# counter-mega8.net
KiCad netlist of a schematic drawn in EAGLE
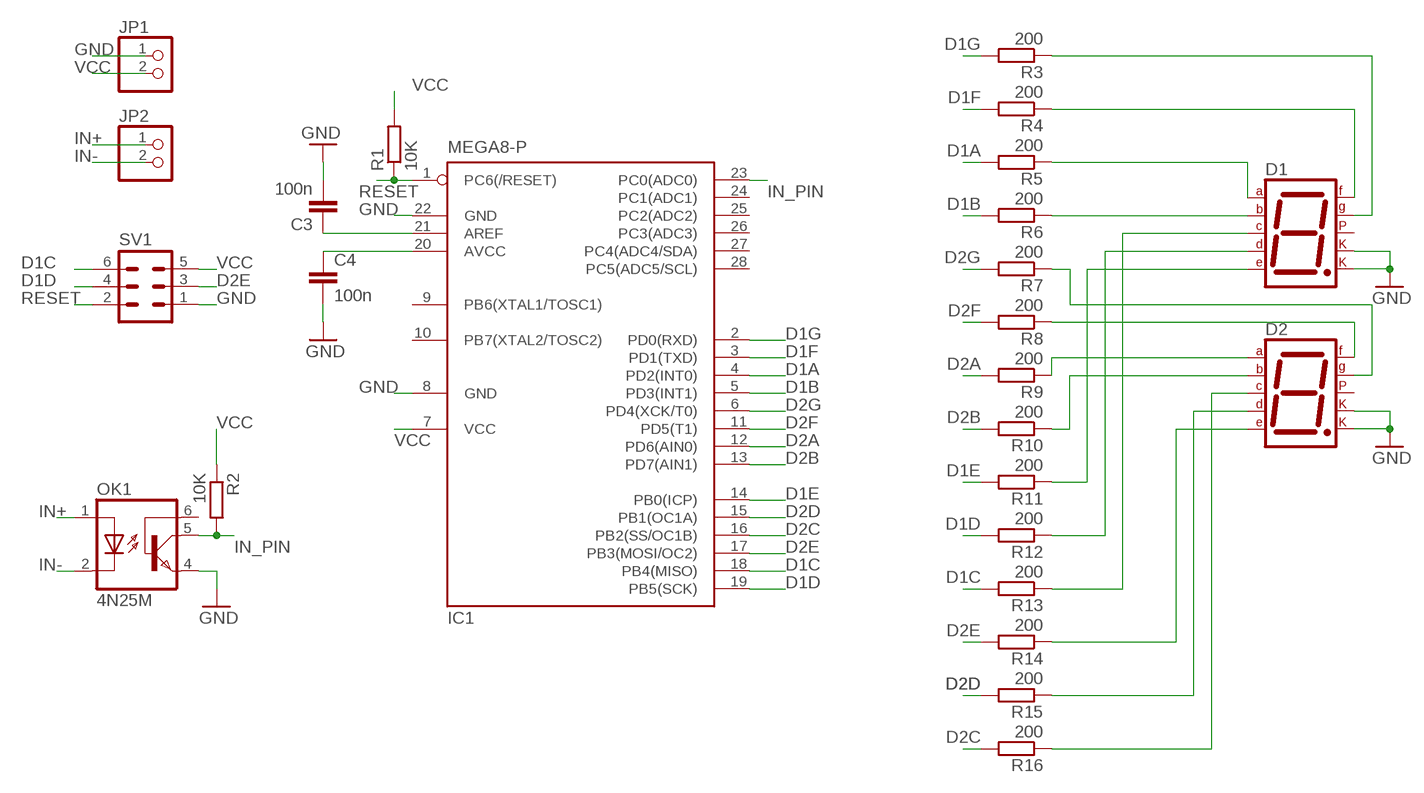
[diagram p0: schematic, sheet 1]

(export (version "E")
  (design (tool "Eeschema 10.0.6"))
  (components
    (comp (ref "C3")
      (value "100n")
      (footprint "eagle-import:C1206")
      (libsource (lib "eagle-import") (part "C-EUC1206"))
    )
    (comp (ref "C4")
      (value "100n")
      (footprint "eagle-import:C1206")
      (libsource (lib "eagle-import") (part "C-EUC1206"))
    )
    (comp (ref "D1")
      (value "7SEG-CK")
      (footprint "eagle-import:7SEG-13")
      (libsource (lib "eagle-import") (part "7SEG-CK"))
    )
    (comp (ref "D2")
      (value "7SEG-CK")
      (footprint "eagle-import:7SEG-13")
      (libsource (lib "eagle-import") (part "7SEG-CK"))
    )
    (comp (ref "IC1")
      (value "MEGA8-P")
      (footprint "eagle-import:DIL28-3")
      (libsource (lib "eagle-import") (part "MEGA8-P"))
    )
    (comp (ref "JP1")
      (value "PINHD-1X2/90")
      (footprint "eagle-import:1X02_90")
      (libsource (lib "eagle-import") (part "PINHD-1X2/90"))
    )
    (comp (ref "JP2")
      (value "PINHD-1X2/90")
      (footprint "eagle-import:1X02_90")
      (libsource (lib "eagle-import") (part "PINHD-1X2/90"))
    )
    (comp (ref "OK1")
      (value "4N25M")
      (footprint "eagle-import:DIL06")
      (fields (field (name "MPN") "4N25-M"))
      (libsource (lib "eagle-import") (part "4N?M25"))
    )
    (comp (ref "R1")
      (value "10K")
      (footprint "eagle-import:R1206")
      (libsource (lib "eagle-import") (part "R-EU_R1206"))
    )
    (comp (ref "R2")
      (value "10K")
      (footprint "eagle-import:R1206")
      (libsource (lib "eagle-import") (part "R-EU_R1206"))
    )
    (comp (ref "R3")
      (value "200")
      (footprint "eagle-import:R1206")
      (libsource (lib "eagle-import") (part "R-EU_R1206"))
    )
    (comp (ref "R4")
      (value "200")
      (footprint "eagle-import:R1206")
      (libsource (lib "eagle-import") (part "R-EU_R1206"))
    )
    (comp (ref "R5")
      (value "200")
      (footprint "eagle-import:R1206")
      (libsource (lib "eagle-import") (part "R-EU_R1206"))
    )
    (comp (ref "R6")
      (value "200")
      (footprint "eagle-import:R1206")
      (libsource (lib "eagle-import") (part "R-EU_R1206"))
    )
    (comp (ref "R7")
      (value "200")
      (footprint "eagle-import:R1206")
      (libsource (lib "eagle-import") (part "R-EU_R1206"))
    )
    (comp (ref "R8")
      (value "200")
      (footprint "eagle-import:R1206")
      (libsource (lib "eagle-import") (part "R-EU_R1206"))
    )
    (comp (ref "R9")
      (value "200")
      (footprint "eagle-import:R1206")
      (libsource (lib "eagle-import") (part "R-EU_R1206"))
    )
    (comp (ref "R10")
      (value "200")
      (footprint "eagle-import:R1206")
      (libsource (lib "eagle-import") (part "R-EU_R1206"))
    )
    (comp (ref "R11")
      (value "200")
      (footprint "eagle-import:R1206")
      (libsource (lib "eagle-import") (part "R-EU_R1206"))
    )
    (comp (ref "R12")
      (value "200")
      (footprint "eagle-import:R1206")
      (libsource (lib "eagle-import") (part "R-EU_R1206"))
    )
    (comp (ref "R13")
      (value "200")
      (footprint "eagle-import:R1206")
      (libsource (lib "eagle-import") (part "R-EU_R1206"))
    )
    (comp (ref "R14")
      (value "200")
      (footprint "eagle-import:R1206")
      (libsource (lib "eagle-import") (part "R-EU_R1206"))
    )
    (comp (ref "R15")
      (value "200")
      (footprint "eagle-import:R1206")
      (libsource (lib "eagle-import") (part "R-EU_R1206"))
    )
    (comp (ref "R16")
      (value "200")
      (footprint "eagle-import:R1206")
      (libsource (lib "eagle-import") (part "R-EU_R1206"))
    )
    (comp (ref "SV1")
      (value "MA03-2")
      (footprint "eagle-import:MA03-2")
      (libsource (lib "eagle-import") (part "MA03-2"))
    )
  )
  (nets
    (net (code "1") (name "/D1A") (class "Default")
      (node (ref "IC1") (pin "4") (pinfunction "PD2(INT0)_4") (pintype "bidirectional"))
      (node (ref "R5") (pin "2") (pinfunction "2_2") (pintype "passive"))
    )
    (net (code "2") (name "/D1B") (class "Default")
      (node (ref "IC1") (pin "5") (pinfunction "PD3(INT1)_5") (pintype "bidirectional"))
      (node (ref "R6") (pin "2") (pinfunction "2_2") (pintype "passive"))
    )
    (net (code "3") (name "/D1C") (class "Default")
      (node (ref "IC1") (pin "18") (pinfunction "PB4(MISO)_18") (pintype "bidirectional"))
      (node (ref "R13") (pin "2") (pinfunction "2_2") (pintype "passive"))
      (node (ref "SV1") (pin "6") (pinfunction "6_6") (pintype "passive"))
    )
    (net (code "4") (name "/D1D") (class "Default")
      (node (ref "IC1") (pin "19") (pinfunction "PB5(SCK)_19") (pintype "bidirectional"))
      (node (ref "R12") (pin "2") (pinfunction "2_2") (pintype "passive"))
      (node (ref "SV1") (pin "4") (pinfunction "4_4") (pintype "passive"))
    )
    (net (code "5") (name "/D1E") (class "Default")
      (node (ref "IC1") (pin "14") (pinfunction "PB0(ICP)_14") (pintype "bidirectional"))
      (node (ref "R11") (pin "2") (pinfunction "2_2") (pintype "passive"))
    )
    (net (code "6") (name "/D1F") (class "Default")
      (node (ref "IC1") (pin "3") (pinfunction "PD1(TXD)_3") (pintype "bidirectional"))
      (node (ref "R4") (pin "2") (pinfunction "2_2") (pintype "passive"))
    )
    (net (code "7") (name "/D1G") (class "Default")
      (node (ref "IC1") (pin "2") (pinfunction "PD0(RXD)_2") (pintype "bidirectional"))
      (node (ref "R3") (pin "2") (pinfunction "2_2") (pintype "passive"))
    )
    (net (code "8") (name "/D2A") (class "Default")
      (node (ref "IC1") (pin "12") (pinfunction "PD6(AIN0)_12") (pintype "bidirectional"))
      (node (ref "R9") (pin "2") (pinfunction "2_2") (pintype "passive"))
    )
    (net (code "9") (name "/D2B") (class "Default")
      (node (ref "IC1") (pin "13") (pinfunction "PD7(AIN1)_13") (pintype "bidirectional"))
      (node (ref "R10") (pin "2") (pinfunction "2_2") (pintype "passive"))
    )
    (net (code "10") (name "/D2C") (class "Default")
      (node (ref "IC1") (pin "16") (pinfunction "PB2(SS/OC1B)_16") (pintype "bidirectional"))
      (node (ref "R16") (pin "2") (pinfunction "2_2") (pintype "passive"))
    )
    (net (code "11") (name "/D2D") (class "Default")
      (node (ref "IC1") (pin "15") (pinfunction "PB1(OC1A)_15") (pintype "bidirectional"))
      (node (ref "R15") (pin "2") (pinfunction "2_2") (pintype "passive"))
    )
    (net (code "12") (name "/D2E") (class "Default")
      (node (ref "IC1") (pin "17") (pinfunction "PB3(MOSI/OC2)_17") (pintype "bidirectional"))
      (node (ref "R14") (pin "2") (pinfunction "2_2") (pintype "passive"))
      (node (ref "SV1") (pin "3") (pinfunction "3_3") (pintype "passive"))
    )
    (net (code "13") (name "/D2F") (class "Default")
      (node (ref "IC1") (pin "11") (pinfunction "PD5(T1)_11") (pintype "bidirectional"))
      (node (ref "R8") (pin "2") (pinfunction "2_2") (pintype "passive"))
    )
    (net (code "14") (name "/D2G") (class "Default")
      (node (ref "IC1") (pin "6") (pinfunction "PD4(XCK/T0)_6") (pintype "bidirectional"))
      (node (ref "R7") (pin "2") (pinfunction "2_2") (pintype "passive"))
    )
    (net (code "15") (name "/IN+") (class "Default")
      (node (ref "JP2") (pin "1") (pinfunction "1_1") (pintype "passive"))
      (node (ref "OK1") (pin "1") (pinfunction "A_1") (pintype "passive"))
    )
    (net (code "16") (name "/IN-") (class "Default")
      (node (ref "JP2") (pin "2") (pinfunction "2_2") (pintype "passive"))
      (node (ref "OK1") (pin "2") (pinfunction "C_2") (pintype "passive"))
    )
    (net (code "17") (name "/IN_PIN") (class "Default")
      (node (ref "IC1") (pin "23") (pinfunction "PC0(ADC0)_23") (pintype "bidirectional"))
      (node (ref "OK1") (pin "5") (pinfunction "COL_5") (pintype "passive"))
      (node (ref "R2") (pin "2") (pinfunction "2_2") (pintype "passive"))
    )
    (net (code "18") (name "/RESET") (class "Default")
      (node (ref "IC1") (pin "1") (pinfunction "PC6(/RESET)_1") (pintype "bidirectional"))
      (node (ref "R1") (pin "1") (pinfunction "1_1") (pintype "passive"))
      (node (ref "SV1") (pin "2") (pinfunction "2_2") (pintype "passive"))
    )
    (net (code "19") (name "/VCC") (class "Default")
      (node (ref "IC1") (pin "7") (pinfunction "VCC_7") (pintype "power_in"))
      (node (ref "JP1") (pin "2") (pinfunction "2_2") (pintype "passive"))
      (node (ref "R1") (pin "2") (pinfunction "2_2") (pintype "passive"))
      (node (ref "R2") (pin "1") (pinfunction "1_1") (pintype "passive"))
      (node (ref "SV1") (pin "5") (pinfunction "5_5") (pintype "passive"))
    )
    (net (code "20") (name "GND") (class "Default")
      (node (ref "C3") (pin "2") (pinfunction "2_2") (pintype "passive"))
      (node (ref "C4") (pin "2") (pinfunction "2_2") (pintype "passive"))
      (node (ref "D1") (pin "3") (pinfunction "CK1_3") (pintype "passive"))
      (node (ref "D1") (pin "8") (pinfunction "CK2_8") (pintype "passive"))
      (node (ref "D2") (pin "3") (pinfunction "CK1_3") (pintype "passive"))
      (node (ref "D2") (pin "8") (pinfunction "CK2_8") (pintype "passive"))
      (node (ref "IC1") (pin "22") (pinfunction "GND_22") (pintype "power_in"))
      (node (ref "IC1") (pin "8") (pinfunction "GND_8") (pintype "power_in"))
      (node (ref "JP1") (pin "1") (pinfunction "1_1") (pintype "passive"))
      (node (ref "OK1") (pin "4") (pinfunction "EMI_4") (pintype "passive"))
      (node (ref "SV1") (pin "1") (pinfunction "1_1") (pintype "passive"))
    )
    (net (code "21") (name "Net-(D1-A)") (class "Default")
      (node (ref "D1") (pin "7") (pinfunction "A_7") (pintype "passive"))
      (node (ref "R5") (pin "1") (pinfunction "1_1") (pintype "passive"))
    )
    (net (code "22") (name "Net-(D1-B)") (class "Default")
      (node (ref "D1") (pin "6") (pinfunction "B_6") (pintype "passive"))
      (node (ref "R6") (pin "1") (pinfunction "1_1") (pintype "passive"))
    )
    (net (code "23") (name "Net-(D1-C)") (class "Default")
      (node (ref "D1") (pin "4") (pinfunction "C_4") (pintype "passive"))
      (node (ref "R13") (pin "1") (pinfunction "1_1") (pintype "passive"))
    )
    (net (code "24") (name "Net-(D1-D)") (class "Default")
      (node (ref "D1") (pin "2") (pinfunction "D_2") (pintype "passive"))
      (node (ref "R12") (pin "1") (pinfunction "1_1") (pintype "passive"))
    )
    (net (code "25") (name "Net-(D1-E)") (class "Default")
      (node (ref "D1") (pin "1") (pinfunction "E_1") (pintype "passive"))
      (node (ref "R11") (pin "1") (pinfunction "1_1") (pintype "passive"))
    )
    (net (code "26") (name "Net-(D1-F)") (class "Default")
      (node (ref "D1") (pin "9") (pinfunction "F_9") (pintype "passive"))
      (node (ref "R4") (pin "1") (pinfunction "1_1") (pintype "passive"))
    )
    (net (code "27") (name "Net-(D1-G)") (class "Default")
      (node (ref "D1") (pin "10") (pinfunction "G_10") (pintype "passive"))
      (node (ref "R3") (pin "1") (pinfunction "1_1") (pintype "passive"))
    )
    (net (code "28") (name "Net-(D2-A)") (class "Default")
      (node (ref "D2") (pin "7") (pinfunction "A_7") (pintype "passive"))
      (node (ref "R9") (pin "1") (pinfunction "1_1") (pintype "passive"))
    )
    (net (code "29") (name "Net-(D2-B)") (class "Default")
      (node (ref "D2") (pin "6") (pinfunction "B_6") (pintype "passive"))
      (node (ref "R10") (pin "1") (pinfunction "1_1") (pintype "passive"))
    )
    (net (code "30") (name "Net-(D2-C)") (class "Default")
      (node (ref "D2") (pin "4") (pinfunction "C_4") (pintype "passive"))
      (node (ref "R16") (pin "1") (pinfunction "1_1") (pintype "passive"))
    )
    (net (code "31") (name "Net-(D2-D)") (class "Default")
      (node (ref "D2") (pin "2") (pinfunction "D_2") (pintype "passive"))
      (node (ref "R15") (pin "1") (pinfunction "1_1") (pintype "passive"))
    )
    (net (code "32") (name "Net-(D2-E)") (class "Default")
      (node (ref "D2") (pin "1") (pinfunction "E_1") (pintype "passive"))
      (node (ref "R14") (pin "1") (pinfunction "1_1") (pintype "passive"))
    )
    (net (code "33") (name "Net-(D2-F)") (class "Default")
      (node (ref "D2") (pin "9") (pinfunction "F_9") (pintype "passive"))
      (node (ref "R8") (pin "1") (pinfunction "1_1") (pintype "passive"))
    )
    (net (code "34") (name "Net-(D2-G)") (class "Default")
      (node (ref "D2") (pin "10") (pinfunction "G_10") (pintype "passive"))
      (node (ref "R7") (pin "1") (pinfunction "1_1") (pintype "passive"))
    )
    (net (code "35") (name "Net-(IC1-AREF)") (class "Default")
      (node (ref "C3") (pin "1") (pinfunction "1_1") (pintype "passive"))
      (node (ref "IC1") (pin "21") (pinfunction "AREF_21") (pintype "passive"))
    )
    (net (code "36") (name "Net-(IC1-AVCC)") (class "Default")
      (node (ref "C4") (pin "1") (pinfunction "1_1") (pintype "passive"))
      (node (ref "IC1") (pin "20") (pinfunction "AVCC_20") (pintype "power_in"))
    )
    (net (code "37") (name "unconnected-(D1-DP-Pad5)") (class "Default")
      (node (ref "D1") (pin "5") (pinfunction "DP_5") (pintype "passive"))
    )
    (net (code "38") (name "unconnected-(D2-DP-Pad5)") (class "Default")
      (node (ref "D2") (pin "5") (pinfunction "DP_5") (pintype "passive"))
    )
    (net (code "39") (name "unconnected-(IC1-PB6(XTAL1{slash}TOSC1)-Pad9)") (class "Default")
      (node (ref "IC1") (pin "9") (pinfunction "PB6(XTAL1/TOSC1)_9") (pintype "bidirectional"))
    )
    (net (code "40") (name "unconnected-(IC1-PB7(XTAL2{slash}TOSC2)-Pad10)") (class "Default")
      (node (ref "IC1") (pin "10") (pinfunction "PB7(XTAL2/TOSC2)_10") (pintype "bidirectional"))
    )
    (net (code "41") (name "unconnected-(IC1-PC1(ADC1)-Pad24)") (class "Default")
      (node (ref "IC1") (pin "24") (pinfunction "PC1(ADC1)_24") (pintype "bidirectional"))
    )
    (net (code "42") (name "unconnected-(IC1-PC2(ADC2)-Pad25)") (class "Default")
      (node (ref "IC1") (pin "25") (pinfunction "PC2(ADC2)_25") (pintype "bidirectional"))
    )
    (net (code "43") (name "unconnected-(IC1-PC3(ADC3)-Pad26)") (class "Default")
      (node (ref "IC1") (pin "26") (pinfunction "PC3(ADC3)_26") (pintype "bidirectional"))
    )
    (net (code "44") (name "unconnected-(IC1-PC4(ADC4{slash}SDA)-Pad27)") (class "Default")
      (node (ref "IC1") (pin "27") (pinfunction "PC4(ADC4/SDA)_27") (pintype "bidirectional"))
    )
    (net (code "45") (name "unconnected-(IC1-PC5(ADC5{slash}SCL)-Pad28)") (class "Default")
      (node (ref "IC1") (pin "28") (pinfunction "PC5(ADC5/SCL)_28") (pintype "bidirectional"))
    )
    (net (code "46") (name "unconnected-(OK1-BAS-Pad6)") (class "Default")
      (node (ref "OK1") (pin "6") (pinfunction "BAS_6") (pintype "passive"))
    )
  )
)
